# 3w-rgb-led-connector-mk-7_1.net
KiCad netlist of a schematic drawn in EAGLE
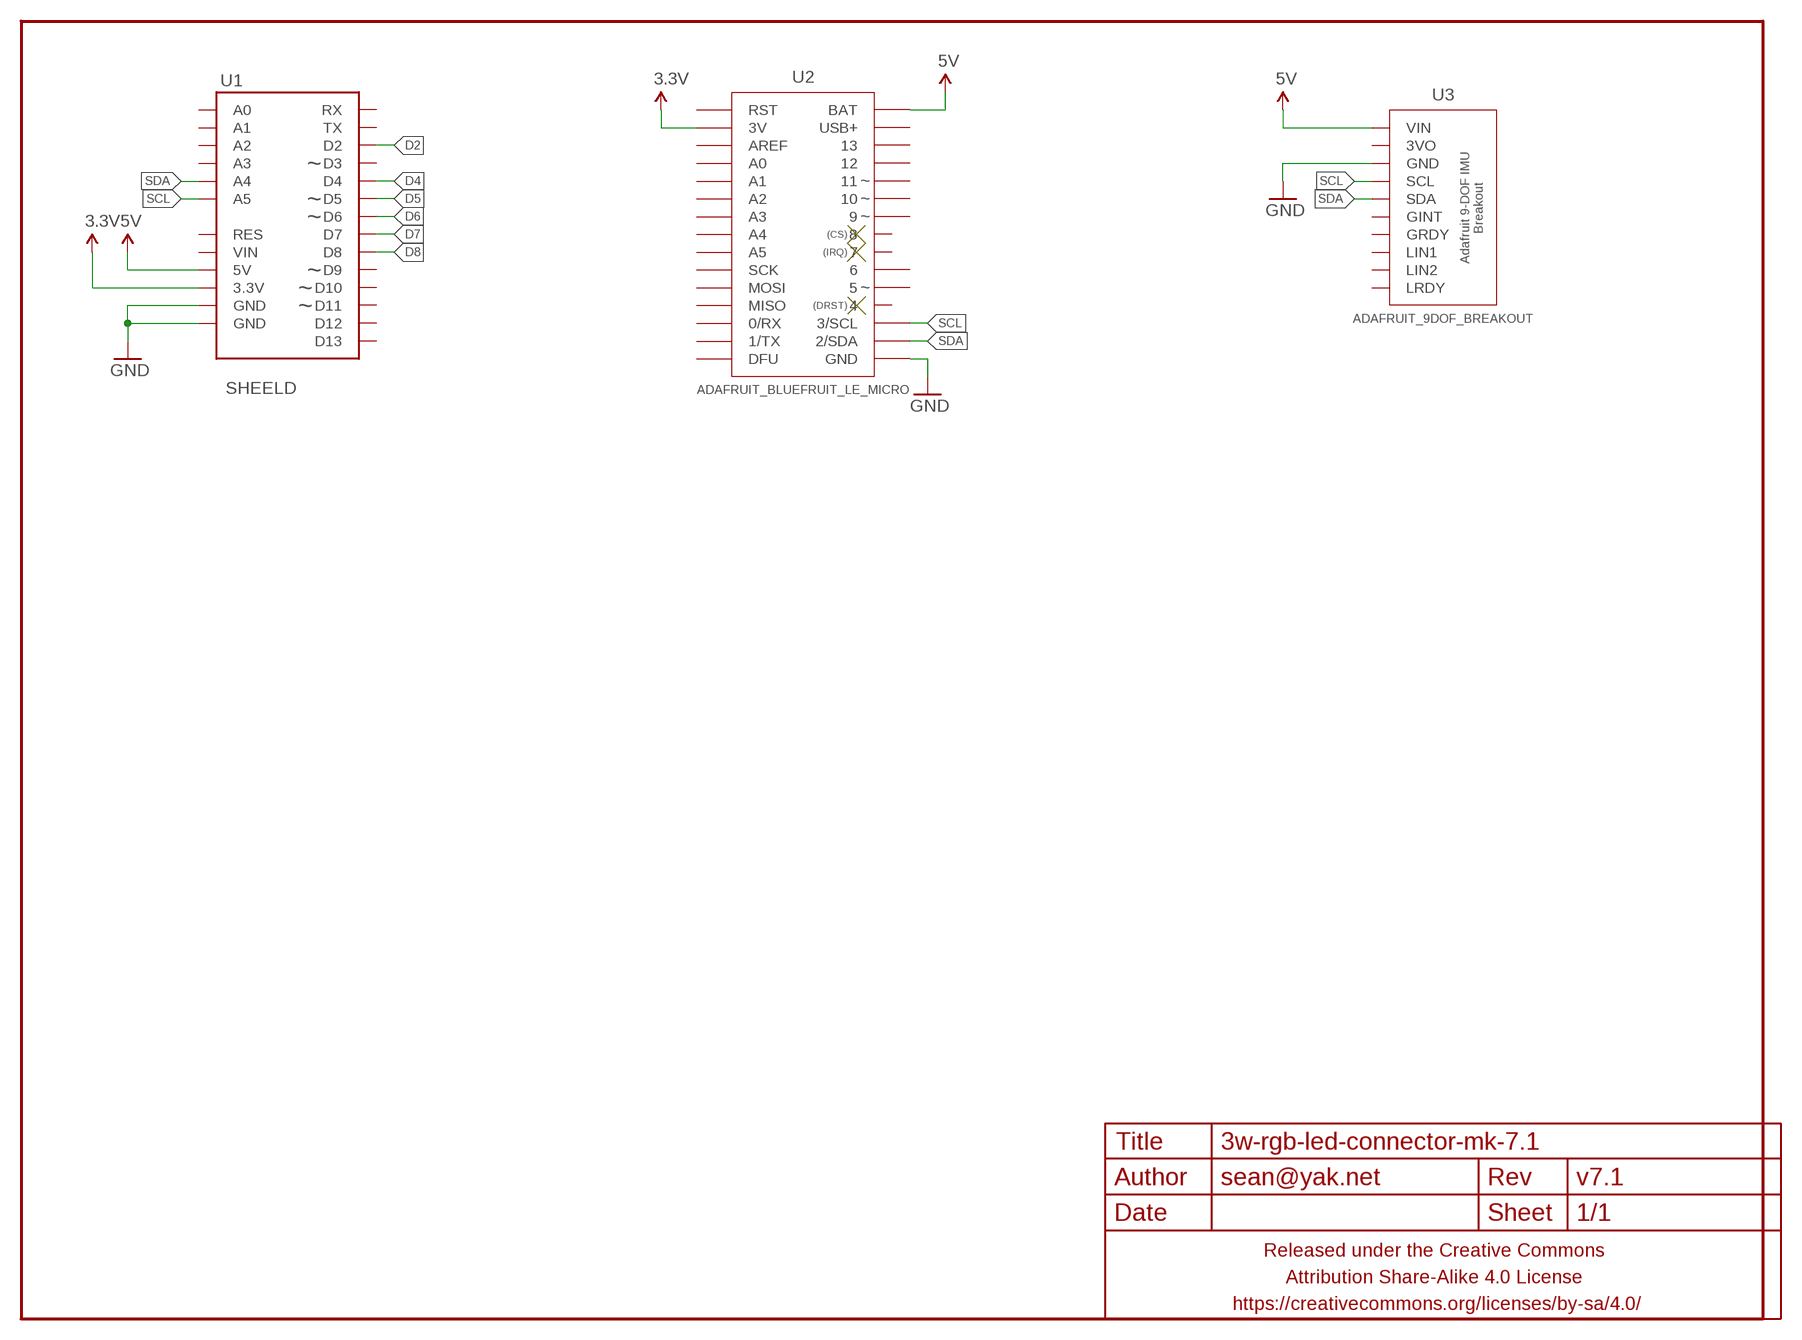
[diagram p0: schematic, sheet 1]

(export (version "E")
  (design (tool "Eeschema 10.0.6"))
  (components
    (comp (ref "FRAME1")
      (value "FRAME-LETTERNO_PACKAGE")
      (footprint "eagle-import:DUMMY")
      (fields (field (name "DESIGNER") "sean@yak.net") (field (name "VERSION") "v7.1"))
      (libsource (lib "eagle-import") (part "FRAME-LETTERNO_PACKAGE"))
    )
    (comp (ref "U1")
      (value "SHEELD")
      (footprint "eagle-import:ARDUINO_SHIELD_NOOUTLINE_INSIDE_SMALLER")
      (libsource (lib "eagle-import") (part "ARDUINO_SHIELD_SMALLER"))
    )
    (comp (ref "U2")
      (value "ADAFRUIT_BLUEFRUIT_LE_MICRO")
      (footprint "eagle-import:ADAFRUIT_BLUEFRUIT_LE_MICRO")
      (libsource (lib "eagle-import") (part "ADAFRUIT_BLUEFRUIT_LE_MICRO"))
    )
    (comp (ref "U3")
      (value "ADAFRUIT_9DOF_BREAKOUT")
      (footprint "eagle-import:ADAFRUIT_9DOF_BREAKOUT")
      (libsource (lib "eagle-import") (part "ADAFRUIT_9DOF_BREAKOUT"))
    )
  )
  (nets
    (net (code "1") (name "3.3V") (class "Default")
      (node (ref "U1") (pin "3.3V") (pinfunction "3.3V_3.3V") (pintype "bidirectional"))
      (node (ref "U2") (pin "3V3") (pinfunction "3V_3V3") (pintype "bidirectional"))
    )
    (net (code "2") (name "5V") (class "Default")
      (node (ref "U1") (pin "5V") (pinfunction "5V_5V") (pintype "bidirectional"))
      (node (ref "U2") (pin "BAT") (pinfunction "BAT_BAT") (pintype "bidirectional"))
      (node (ref "U3") (pin "VIN") (pinfunction "VIN_VIN") (pintype "bidirectional"))
    )
    (net (code "3") (name "D2") (class "Default")
      (node (ref "U1") (pin "D2") (pinfunction "D2_D2") (pintype "bidirectional"))
    )
    (net (code "4") (name "D4") (class "Default")
      (node (ref "U1") (pin "D4") (pinfunction "D4_D4") (pintype "bidirectional"))
    )
    (net (code "5") (name "D5") (class "Default")
      (node (ref "U1") (pin "D5") (pinfunction "D5_D5") (pintype "bidirectional"))
    )
    (net (code "6") (name "D6") (class "Default")
      (node (ref "U1") (pin "D6") (pinfunction "D6_D6") (pintype "bidirectional"))
    )
    (net (code "7") (name "D7") (class "Default")
      (node (ref "U1") (pin "D7") (pinfunction "D7_D7") (pintype "bidirectional"))
    )
    (net (code "8") (name "D8") (class "Default")
      (node (ref "U1") (pin "D8") (pinfunction "D8_D8") (pintype "bidirectional"))
    )
    (net (code "9") (name "GND") (class "Default")
      (node (ref "U1") (pin "GND@0") (pinfunction "GND_GND@0") (pintype "bidirectional"))
      (node (ref "U1") (pin "GND@1") (pinfunction "GND_GND@1") (pintype "bidirectional"))
      (node (ref "U2") (pin "GND@1") (pinfunction "GND_GND@1") (pintype "bidirectional"))
      (node (ref "U2") (pin "GND@2") (pinfunction "GND_GND@2") (pintype "bidirectional"))
      (node (ref "U2") (pin "GND@3") (pinfunction "GND_GND@3") (pintype "bidirectional"))
      (node (ref "U3") (pin "GND") (pinfunction "GND_GND") (pintype "bidirectional"))
    )
    (net (code "10") (name "SCL") (class "Default")
      (node (ref "U1") (pin "A5") (pinfunction "A5_A5") (pintype "bidirectional"))
      (node (ref "U2") (pin "3/SCL") (pinfunction "3/SCL_3/SCL") (pintype "bidirectional"))
      (node (ref "U3") (pin "SCL") (pinfunction "SCL_SCL") (pintype "bidirectional"))
    )
    (net (code "11") (name "SDA") (class "Default")
      (node (ref "U1") (pin "A4") (pinfunction "A4_A4") (pintype "bidirectional"))
      (node (ref "U2") (pin "2/SDA") (pinfunction "2/SDA_2/SDA") (pintype "bidirectional"))
      (node (ref "U3") (pin "SDA") (pinfunction "SDA_SDA") (pintype "bidirectional"))
    )
    (net (code "12") (name "unconnected-(U1-PadA0)") (class "Default")
      (node (ref "U1") (pin "A0") (pinfunction "A0_A0") (pintype "bidirectional"))
    )
    (net (code "13") (name "unconnected-(U1-PadA1)") (class "Default")
      (node (ref "U1") (pin "A1") (pinfunction "A1_A1") (pintype "bidirectional"))
    )
    (net (code "14") (name "unconnected-(U1-PadA2)") (class "Default")
      (node (ref "U1") (pin "A2") (pinfunction "A2_A2") (pintype "bidirectional"))
    )
    (net (code "15") (name "unconnected-(U1-PadA3)") (class "Default")
      (node (ref "U1") (pin "A3") (pinfunction "A3_A3") (pintype "bidirectional"))
    )
    (net (code "16") (name "unconnected-(U1-PadD3)") (class "Default")
      (node (ref "U1") (pin "D3") (pinfunction "D3_D3") (pintype "bidirectional"))
    )
    (net (code "17") (name "unconnected-(U1-PadD9)") (class "Default")
      (node (ref "U1") (pin "D9") (pinfunction "D9_D9") (pintype "bidirectional"))
    )
    (net (code "18") (name "unconnected-(U1-PadD10)") (class "Default")
      (node (ref "U1") (pin "D10") (pinfunction "D10_D10") (pintype "bidirectional"))
    )
    (net (code "19") (name "unconnected-(U1-PadD11)") (class "Default")
      (node (ref "U1") (pin "D11") (pinfunction "D11_D11") (pintype "bidirectional"))
    )
    (net (code "20") (name "unconnected-(U1-PadD12)") (class "Default")
      (node (ref "U1") (pin "D12") (pinfunction "D12_D12") (pintype "bidirectional"))
    )
    (net (code "21") (name "unconnected-(U1-PadD13)") (class "Default")
      (node (ref "U1") (pin "D13") (pinfunction "D13_D13") (pintype "bidirectional"))
    )
    (net (code "22") (name "unconnected-(U1-PadRES)") (class "Default")
      (node (ref "U1") (pin "RES") (pinfunction "RES_RES") (pintype "bidirectional"))
    )
    (net (code "23") (name "unconnected-(U1-PadRX)") (class "Default")
      (node (ref "U1") (pin "RX") (pinfunction "RX_RX") (pintype "bidirectional"))
    )
    (net (code "24") (name "unconnected-(U1-PadTX)") (class "Default")
      (node (ref "U1") (pin "TX") (pinfunction "TX_TX") (pintype "bidirectional"))
    )
    (net (code "25") (name "unconnected-(U1-PadVIN)") (class "Default")
      (node (ref "U1") (pin "VIN") (pinfunction "VIN_VIN") (pintype "bidirectional"))
    )
    (net (code "26") (name "unconnected-(U2-Pad0{slash}RX)") (class "Default")
      (node (ref "U2") (pin "0/RX") (pinfunction "0/RX_0/RX") (pintype "bidirectional"))
    )
    (net (code "27") (name "unconnected-(U2-Pad1{slash}TX)") (class "Default")
      (node (ref "U2") (pin "1/TX") (pinfunction "1/TX_1/TX") (pintype "bidirectional"))
    )
    (net (code "28") (name "unconnected-(U2-Pad4)") (class "Default")
      (node (ref "U2") (pin "4") (pinfunction "4_4") (pintype "bidirectional"))
    )
    (net (code "29") (name "unconnected-(U2-Pad5)") (class "Default")
      (node (ref "U2") (pin "5") (pinfunction "5_5") (pintype "bidirectional"))
    )
    (net (code "30") (name "unconnected-(U2-Pad6)") (class "Default")
      (node (ref "U2") (pin "6") (pinfunction "6_6") (pintype "bidirectional"))
    )
    (net (code "31") (name "unconnected-(U2-Pad7)") (class "Default")
      (node (ref "U2") (pin "7") (pinfunction "7_7") (pintype "bidirectional"))
    )
    (net (code "32") (name "unconnected-(U2-Pad8)") (class "Default")
      (node (ref "U2") (pin "8") (pinfunction "8_8") (pintype "bidirectional"))
    )
    (net (code "33") (name "unconnected-(U2-Pad9)") (class "Default")
      (node (ref "U2") (pin "9") (pinfunction "9_9") (pintype "bidirectional"))
    )
    (net (code "34") (name "unconnected-(U2-Pad10)") (class "Default")
      (node (ref "U2") (pin "10") (pinfunction "10_10") (pintype "bidirectional"))
    )
    (net (code "35") (name "unconnected-(U2-Pad11)") (class "Default")
      (node (ref "U2") (pin "11") (pinfunction "11_11") (pintype "bidirectional"))
    )
    (net (code "36") (name "unconnected-(U2-Pad12)") (class "Default")
      (node (ref "U2") (pin "12") (pinfunction "12_12") (pintype "bidirectional"))
    )
    (net (code "37") (name "unconnected-(U2-Pad13)") (class "Default")
      (node (ref "U2") (pin "13") (pinfunction "13_13") (pintype "bidirectional"))
    )
    (net (code "38") (name "unconnected-(U2-PadA0)") (class "Default")
      (node (ref "U2") (pin "A0") (pinfunction "A0_A0") (pintype "bidirectional"))
    )
    (net (code "39") (name "unconnected-(U2-PadA1)") (class "Default")
      (node (ref "U2") (pin "A1") (pinfunction "A1_A1") (pintype "bidirectional"))
    )
    (net (code "40") (name "unconnected-(U2-PadA2)") (class "Default")
      (node (ref "U2") (pin "A2") (pinfunction "A2_A2") (pintype "bidirectional"))
    )
    (net (code "41") (name "unconnected-(U2-PadA3)") (class "Default")
      (node (ref "U2") (pin "A3") (pinfunction "A3_A3") (pintype "bidirectional"))
    )
    (net (code "42") (name "unconnected-(U2-PadA4)") (class "Default")
      (node (ref "U2") (pin "A4") (pinfunction "A4_A4") (pintype "bidirectional"))
    )
    (net (code "43") (name "unconnected-(U2-PadA5)") (class "Default")
      (node (ref "U2") (pin "A5") (pinfunction "A5_A5") (pintype "bidirectional"))
    )
    (net (code "44") (name "unconnected-(U2-PadAREF)") (class "Default")
      (node (ref "U2") (pin "AREF") (pinfunction "AREF_AREF") (pintype "bidirectional"))
    )
    (net (code "45") (name "unconnected-(U2-PadDFU)") (class "Default")
      (node (ref "U2") (pin "DFU") (pinfunction "DFU_DFU") (pintype "bidirectional"))
    )
    (net (code "46") (name "unconnected-(U2-PadMISO)") (class "Default")
      (node (ref "U2") (pin "MISO") (pinfunction "MISO_MISO") (pintype "bidirectional"))
    )
    (net (code "47") (name "unconnected-(U2-PadMOSI)") (class "Default")
      (node (ref "U2") (pin "MOSI") (pinfunction "MOSI_MOSI") (pintype "bidirectional"))
    )
    (net (code "48") (name "unconnected-(U2-PadRST)") (class "Default")
      (node (ref "U2") (pin "RST") (pinfunction "RST_RST") (pintype "bidirectional"))
    )
    (net (code "49") (name "unconnected-(U2-PadSCK)") (class "Default")
      (node (ref "U2") (pin "SCK") (pinfunction "SCK_SCK") (pintype "bidirectional"))
    )
    (net (code "50") (name "unconnected-(U2-USB+-PadUSB)") (class "Default")
      (node (ref "U2") (pin "USB") (pinfunction "USB+_USB") (pintype "bidirectional"))
    )
    (net (code "51") (name "unconnected-(U3-Pad3VO)") (class "Default")
      (node (ref "U3") (pin "3VO") (pinfunction "3VO_3VO") (pintype "bidirectional"))
    )
    (net (code "52") (name "unconnected-(U3-PadGINT)") (class "Default")
      (node (ref "U3") (pin "GINT") (pinfunction "GINT_GINT") (pintype "bidirectional"))
    )
    (net (code "53") (name "unconnected-(U3-PadGRDY)") (class "Default")
      (node (ref "U3") (pin "GRDY") (pinfunction "GRDY_GRDY") (pintype "bidirectional"))
    )
    (net (code "54") (name "unconnected-(U3-PadLIN1)") (class "Default")
      (node (ref "U3") (pin "LIN1") (pinfunction "LIN1_LIN1") (pintype "bidirectional"))
    )
    (net (code "55") (name "unconnected-(U3-PadLIN2)") (class "Default")
      (node (ref "U3") (pin "LIN2") (pinfunction "LIN2_LIN2") (pintype "bidirectional"))
    )
    (net (code "56") (name "unconnected-(U3-PadLRDY)") (class "Default")
      (node (ref "U3") (pin "LRDY") (pinfunction "LRDY_LRDY") (pintype "bidirectional"))
    )
  )
)
